# reference.net
KiCad netlist of a schematic drawn in Altium Designer
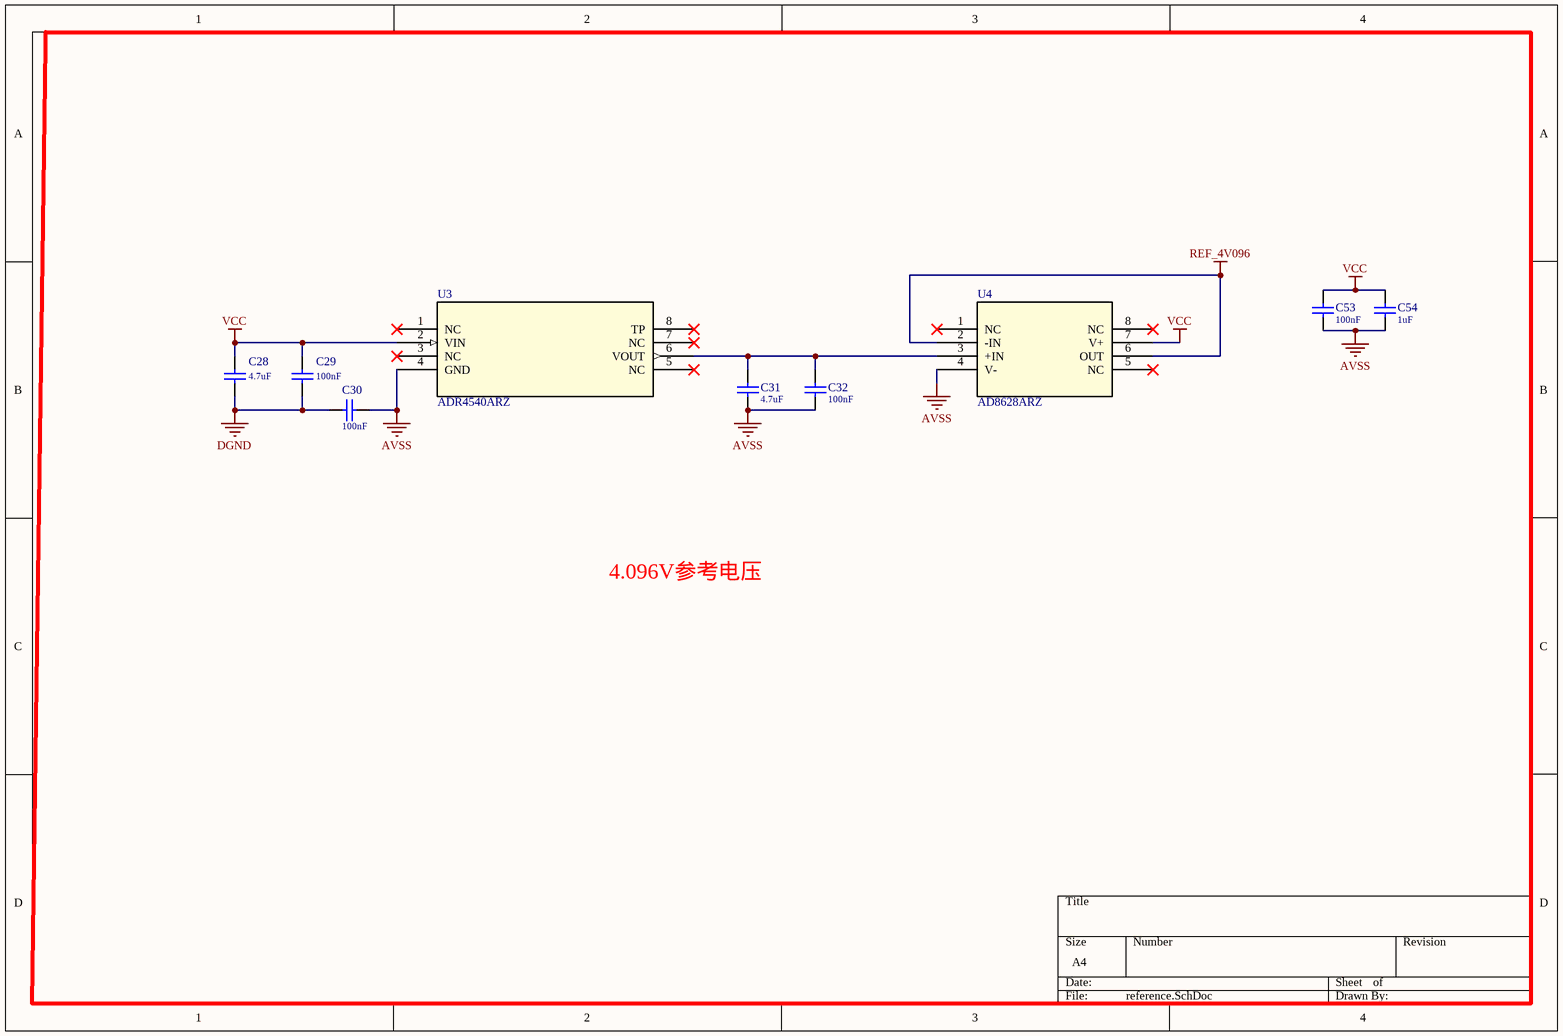
[diagram p0: reference.SchDoc]

(export (version "E")
  (design (tool "Eeschema 10.0.6"))
  (components
    (comp (ref "C28")
      (value "4.7uF")
      (footprint "C0603-L")
      (description "贴片瓷片电容")
      (fields (field (name "Comment") "Cap-S"))
      (libsource (lib "XuZhe") (part "Cap-S"))
    )
    (comp (ref "C29")
      (value "100nF")
      (footprint "C0603-L")
      (description "贴片瓷片电容")
      (fields (field (name "Comment") "Cap-S"))
      (libsource (lib "XuZhe") (part "Cap-S"))
    )
    (comp (ref "C30")
      (value "100nF")
      (footprint "C0603-L")
      (description "贴片瓷片电容")
      (fields (field (name "Comment") "Cap-S"))
      (libsource (lib "XuZhe") (part "Cap-S"))
    )
    (comp (ref "C31")
      (value "4.7uF")
      (footprint "C0603-L")
      (description "贴片瓷片电容")
      (fields (field (name "Comment") "Cap-S"))
      (libsource (lib "XuZhe") (part "Cap-S"))
    )
    (comp (ref "C32")
      (value "100nF")
      (footprint "C0603-L")
      (description "贴片瓷片电容")
      (fields (field (name "Comment") "Cap-S"))
      (libsource (lib "XuZhe") (part "Cap-S"))
    )
    (comp (ref "C53")
      (value "100nF")
      (footprint "C0603-L")
      (description "贴片瓷片电容")
      (fields (field (name "Comment") "Cap-S"))
      (libsource (lib "XuZhe") (part "Cap-S"))
    )
    (comp (ref "C54")
      (value "1uF")
      (footprint "C0603-L")
      (description "贴片瓷片电容")
      (fields (field (name "Comment") "Cap-S"))
      (libsource (lib "XuZhe") (part "Cap-S"))
    )
    (comp (ref "U3")
      (value "ADR4540ARZ")
      (footprint "R_8_ADI")
      (description "No Description Available")
      (fields (field (name "COPYRIGHT") "Copyright (C) 2021 Ultra Librarian. All rights reserved."))
      (libsource (lib "ADR4540ARZ") (part "ADR4540ARZ"))
    )
    (comp (ref "U4")
      (value "AD8628ARZ")
      (footprint "R_8_ADI")
      (description "No Description Available")
      (fields (field (name "COPYRIGHT") "Copyright (C) 2021 Ultra Librarian. All rights reserved."))
      (libsource (lib "AD8628ARZ") (part "AD8628ARZ"))
    )
  )
  (nets
    (net (code "1") (name "AVSS") (class "Default")
      (node (ref "C30") (pin "1") (pinfunction "1_1") (pintype "passive"))
      (node (ref "C31") (pin "1") (pinfunction "1_1") (pintype "passive"))
      (node (ref "C32") (pin "1") (pinfunction "1_1") (pintype "passive"))
      (node (ref "C53") (pin "1") (pinfunction "1_1") (pintype "passive"))
      (node (ref "C54") (pin "1") (pinfunction "1_1") (pintype "passive"))
      (node (ref "U3") (pin "4") (pinfunction "GND_4") (pintype "power_in"))
      (node (ref "U4") (pin "4") (pinfunction "V-_4") (pintype "power_in"))
    )
    (net (code "2") (name "DGND") (class "Default")
      (node (ref "C28") (pin "1") (pinfunction "1_1") (pintype "passive"))
      (node (ref "C29") (pin "1") (pinfunction "1_1") (pintype "passive"))
      (node (ref "C30") (pin "2") (pinfunction "2_2") (pintype "passive"))
    )
    (net (code "3") (name "Net-(U3-VOUT)") (class "Default")
      (node (ref "C31") (pin "2") (pinfunction "2_2") (pintype "passive"))
      (node (ref "C32") (pin "2") (pinfunction "2_2") (pintype "passive"))
      (node (ref "U3") (pin "6") (pinfunction "VOUT_6") (pintype "output"))
      (node (ref "U4") (pin "3") (pinfunction "+IN_3") (pintype "passive"))
    )
    (net (code "4") (name "REF_4V096") (class "Default")
      (node (ref "U4") (pin "2") (pinfunction "-IN_2") (pintype "passive"))
      (node (ref "U4") (pin "6") (pinfunction "OUT_6") (pintype "passive"))
    )
    (net (code "5") (name "VCC") (class "Default")
      (node (ref "C28") (pin "2") (pinfunction "2_2") (pintype "passive"))
      (node (ref "C29") (pin "2") (pinfunction "2_2") (pintype "passive"))
      (node (ref "C53") (pin "2") (pinfunction "2_2") (pintype "passive"))
      (node (ref "C54") (pin "2") (pinfunction "2_2") (pintype "passive"))
      (node (ref "U3") (pin "2") (pinfunction "VIN_2") (pintype "input"))
      (node (ref "U4") (pin "7") (pinfunction "V+_7") (pintype "power_in"))
    )
    (net (code "6") (name "unconnected-(U3-NC-Pad1)") (class "Default")
      (node (ref "U3") (pin "1") (pinfunction "NC_1") (pintype "passive+no_connect"))
    )
    (net (code "7") (name "unconnected-(U3-NC-Pad3)") (class "Default")
      (node (ref "U3") (pin "3") (pinfunction "NC_3") (pintype "passive+no_connect"))
    )
    (net (code "8") (name "unconnected-(U3-NC-Pad5)") (class "Default")
      (node (ref "U3") (pin "5") (pinfunction "NC_5") (pintype "passive+no_connect"))
    )
    (net (code "9") (name "unconnected-(U3-NC-Pad7)") (class "Default")
      (node (ref "U3") (pin "7") (pinfunction "NC_7") (pintype "passive+no_connect"))
    )
    (net (code "10") (name "unconnected-(U3-TP-Pad8)") (class "Default")
      (node (ref "U3") (pin "8") (pinfunction "TP_8") (pintype "passive+no_connect"))
    )
    (net (code "11") (name "unconnected-(U4-NC-Pad1)") (class "Default")
      (node (ref "U4") (pin "1") (pinfunction "NC_1") (pintype "passive+no_connect"))
    )
    (net (code "12") (name "unconnected-(U4-NC-Pad5)") (class "Default")
      (node (ref "U4") (pin "5") (pinfunction "NC_5") (pintype "passive+no_connect"))
    )
    (net (code "13") (name "unconnected-(U4-NC-Pad8)") (class "Default")
      (node (ref "U4") (pin "8") (pinfunction "NC_8") (pintype "passive+no_connect"))
    )
  )
)
